# 5V_Buck.net
KiCad netlist of a schematic drawn in Altium Designer
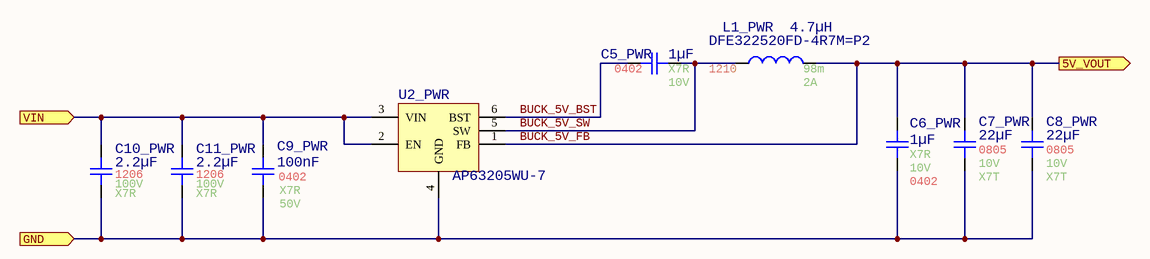
[diagram p0: 5V_Buck.SchDoc]

(export (version "E")
  (design (tool "Eeschema 10.0.6"))
  (components
    (comp (ref "C5_PWR")
      (value "1µF")
      (footprint "Generic 0402 capacitor")
      (description "Cap Cer 1UF 20V X7T 0402")
      (fields
        (field (name "TEMPERATURE COEFFICIENT") "X7R")
        (field (name "VOLTAGE RATING") "10V")
        (field (name "CASE/PACKAGE") "0402")
        (field (name "TOLERANCE") "20%")
        (field (name "Comment") "MAASL105CD7105MFCA01")
      )
      (libsource (lib "Raise Robotics") (part "Unpolarized Capacitor"))
    )
    (comp (ref "C6_PWR")
      (value "1µF")
      (footprint "Generic 0402 capacitor")
      (description "Cap Cer 1UF 20V X7T 0402")
      (fields
        (field (name "TEMPERATURE COEFFICIENT") "X7R")
        (field (name "VOLTAGE RATING") "10V")
        (field (name "CASE/PACKAGE") "0402")
        (field (name "TOLERANCE") "20%")
        (field (name "Comment") "MAASL105CD7105MFCA01")
      )
      (libsource (lib "Raise Robotics") (part "Unpolarized Capacitor"))
    )
    (comp (ref "C7_PWR")
      (value "22µF")
      (footprint "Generic 0805 Cap")
      (description "22 µF ±20% 10V Ceramic Capacitor X7T 0805 (2012 Metric)")
      (fields
        (field (name "TEMPERATURE COEFFICIENT") "X7T")
        (field (name "VOLTAGE RATING") "10V")
        (field (name "CASE/PACKAGE") "0805")
        (field (name "TOLERANCE") "20%")
        (field (name "Comment") "GRT21BD71A226ME13L")
      )
      (libsource (lib "Raise Robotics") (part "Unpolarized Capacitor"))
    )
    (comp (ref "C8_PWR")
      (value "22µF")
      (footprint "Generic 0805 Cap")
      (description "22 µF ±20% 10V Ceramic Capacitor X7T 0805 (2012 Metric)")
      (fields
        (field (name "TEMPERATURE COEFFICIENT") "X7T")
        (field (name "VOLTAGE RATING") "10V")
        (field (name "CASE/PACKAGE") "0805")
        (field (name "TOLERANCE") "20%")
        (field (name "Comment") "GRT21BD71A226ME13L")
      )
      (libsource (lib "Raise Robotics") (part "Unpolarized Capacitor"))
    )
    (comp (ref "C9_PWR")
      (value "100nF")
      (footprint "Generic 0402 capacitor")
      (fields
        (field (name "TEMPERATURE COEFFICIENT") "X7R")
        (field (name "VOLTAGE RATING") "50V")
        (field (name "CASE/PACKAGE") "0402")
        (field (name "TOLERANCE") "10%")
        (field (name "Comment") "GRT155R71H104KE01D")
      )
      (libsource (lib "Raise Robotics") (part "Unpolarized Capacitor"))
    )
    (comp (ref "C10_PWR")
      (value "2.2µF")
      (footprint "Generic 1206 Capacitor")
      (fields
        (field (name "TEMPERATURE COEFFICIENT") "X7R")
        (field (name "VOLTAGE RATING") "100V")
        (field (name "CASE/PACKAGE") "1206")
        (field (name "TOLERANCE") "10%")
        (field (name "Comment") "12061C225K4T2A")
      )
      (libsource (lib "Raise Robotics") (part "Unpolarized Capacitor"))
    )
    (comp (ref "C11_PWR")
      (value "2.2µF")
      (footprint "Generic 1206 Capacitor")
      (fields
        (field (name "TEMPERATURE COEFFICIENT") "X7R")
        (field (name "VOLTAGE RATING") "100V")
        (field (name "CASE/PACKAGE") "1206")
        (field (name "TOLERANCE") "10%")
        (field (name "Comment") "12061C225K4T2A")
      )
      (libsource (lib "Raise Robotics") (part "Unpolarized Capacitor"))
    )
    (comp (ref "L1_PWR")
      (value "DFE322520FD-4R7M=P2")
      (footprint "FP-DFE322520F_D-IPC_A")
      (description "General Purpose Inductor, 4.7uH, 20%, 1 Element, Metal Alloy-Core, SMD, 1210")
      (fields
        (field (name "DCR") "98m")
        (field (name "CURRENT RATING") "2A")
        (field (name "CASE/PACKAGE") "1210")
        (field (name "ALTIUM_VALUE") "4.7µH")
        (field (name "TOLERANCE") "20%")
      )
      (libsource (lib "Raise Robotics") (part "Generic 2 pin inductor"))
    )
    (comp (ref "U2_PWR")
      (value "AP63205WU-7")
      (footprint "TSOT-26-6 - 3.2mm")
      (description "5V fixed step down Buck")
      (libsource (lib "IC") (part "AP63205WU-7"))
    )
  )
  (nets
    (net (code "1") (name "/BUCK_5V_BST") (class "Default")
      (node (ref "C5_PWR") (pin "2") (pinfunction "2_2") (pintype "passive"))
      (node (ref "U2_PWR") (pin "6") (pinfunction "BST_6") (pintype "passive"))
    )
    (net (code "2") (name "/BUCK_5V_FB") (class "Default")
      (node (ref "C6_PWR") (pin "2") (pinfunction "2_2") (pintype "passive"))
      (node (ref "C7_PWR") (pin "2") (pinfunction "2_2") (pintype "passive"))
      (node (ref "C8_PWR") (pin "2") (pinfunction "2_2") (pintype "passive"))
      (node (ref "L1_PWR") (pin "2") (pinfunction "2_2") (pintype "passive"))
      (node (ref "U2_PWR") (pin "1") (pinfunction "FB_1") (pintype "passive"))
    )
    (net (code "3") (name "/BUCK_5V_SW") (class "Default")
      (node (ref "C5_PWR") (pin "1") (pinfunction "1_1") (pintype "passive"))
      (node (ref "L1_PWR") (pin "1") (pinfunction "1_1") (pintype "passive"))
      (node (ref "U2_PWR") (pin "5") (pinfunction "SW_5") (pintype "passive"))
    )
    (net (code "4") (name "/GND") (class "Default")
      (node (ref "C10_PWR") (pin "1") (pinfunction "1_1") (pintype "passive"))
      (node (ref "C11_PWR") (pin "1") (pinfunction "1_1") (pintype "passive"))
      (node (ref "C6_PWR") (pin "1") (pinfunction "1_1") (pintype "passive"))
      (node (ref "C7_PWR") (pin "1") (pinfunction "1_1") (pintype "passive"))
      (node (ref "C8_PWR") (pin "1") (pinfunction "1_1") (pintype "passive"))
      (node (ref "C9_PWR") (pin "2") (pinfunction "2_2") (pintype "passive"))
      (node (ref "U2_PWR") (pin "4") (pinfunction "GND_4") (pintype "passive"))
    )
    (net (code "5") (name "/VIN") (class "Default")
      (node (ref "C10_PWR") (pin "2") (pinfunction "2_2") (pintype "passive"))
      (node (ref "C11_PWR") (pin "2") (pinfunction "2_2") (pintype "passive"))
      (node (ref "C9_PWR") (pin "1") (pinfunction "1_1") (pintype "passive"))
      (node (ref "U2_PWR") (pin "2") (pinfunction "EN_2") (pintype "passive"))
      (node (ref "U2_PWR") (pin "3") (pinfunction "VIN_3") (pintype "passive"))
    )
  )
)
